# hydrogen_sensors_board.net
KiCad netlist of a schematic drawn in EAGLE
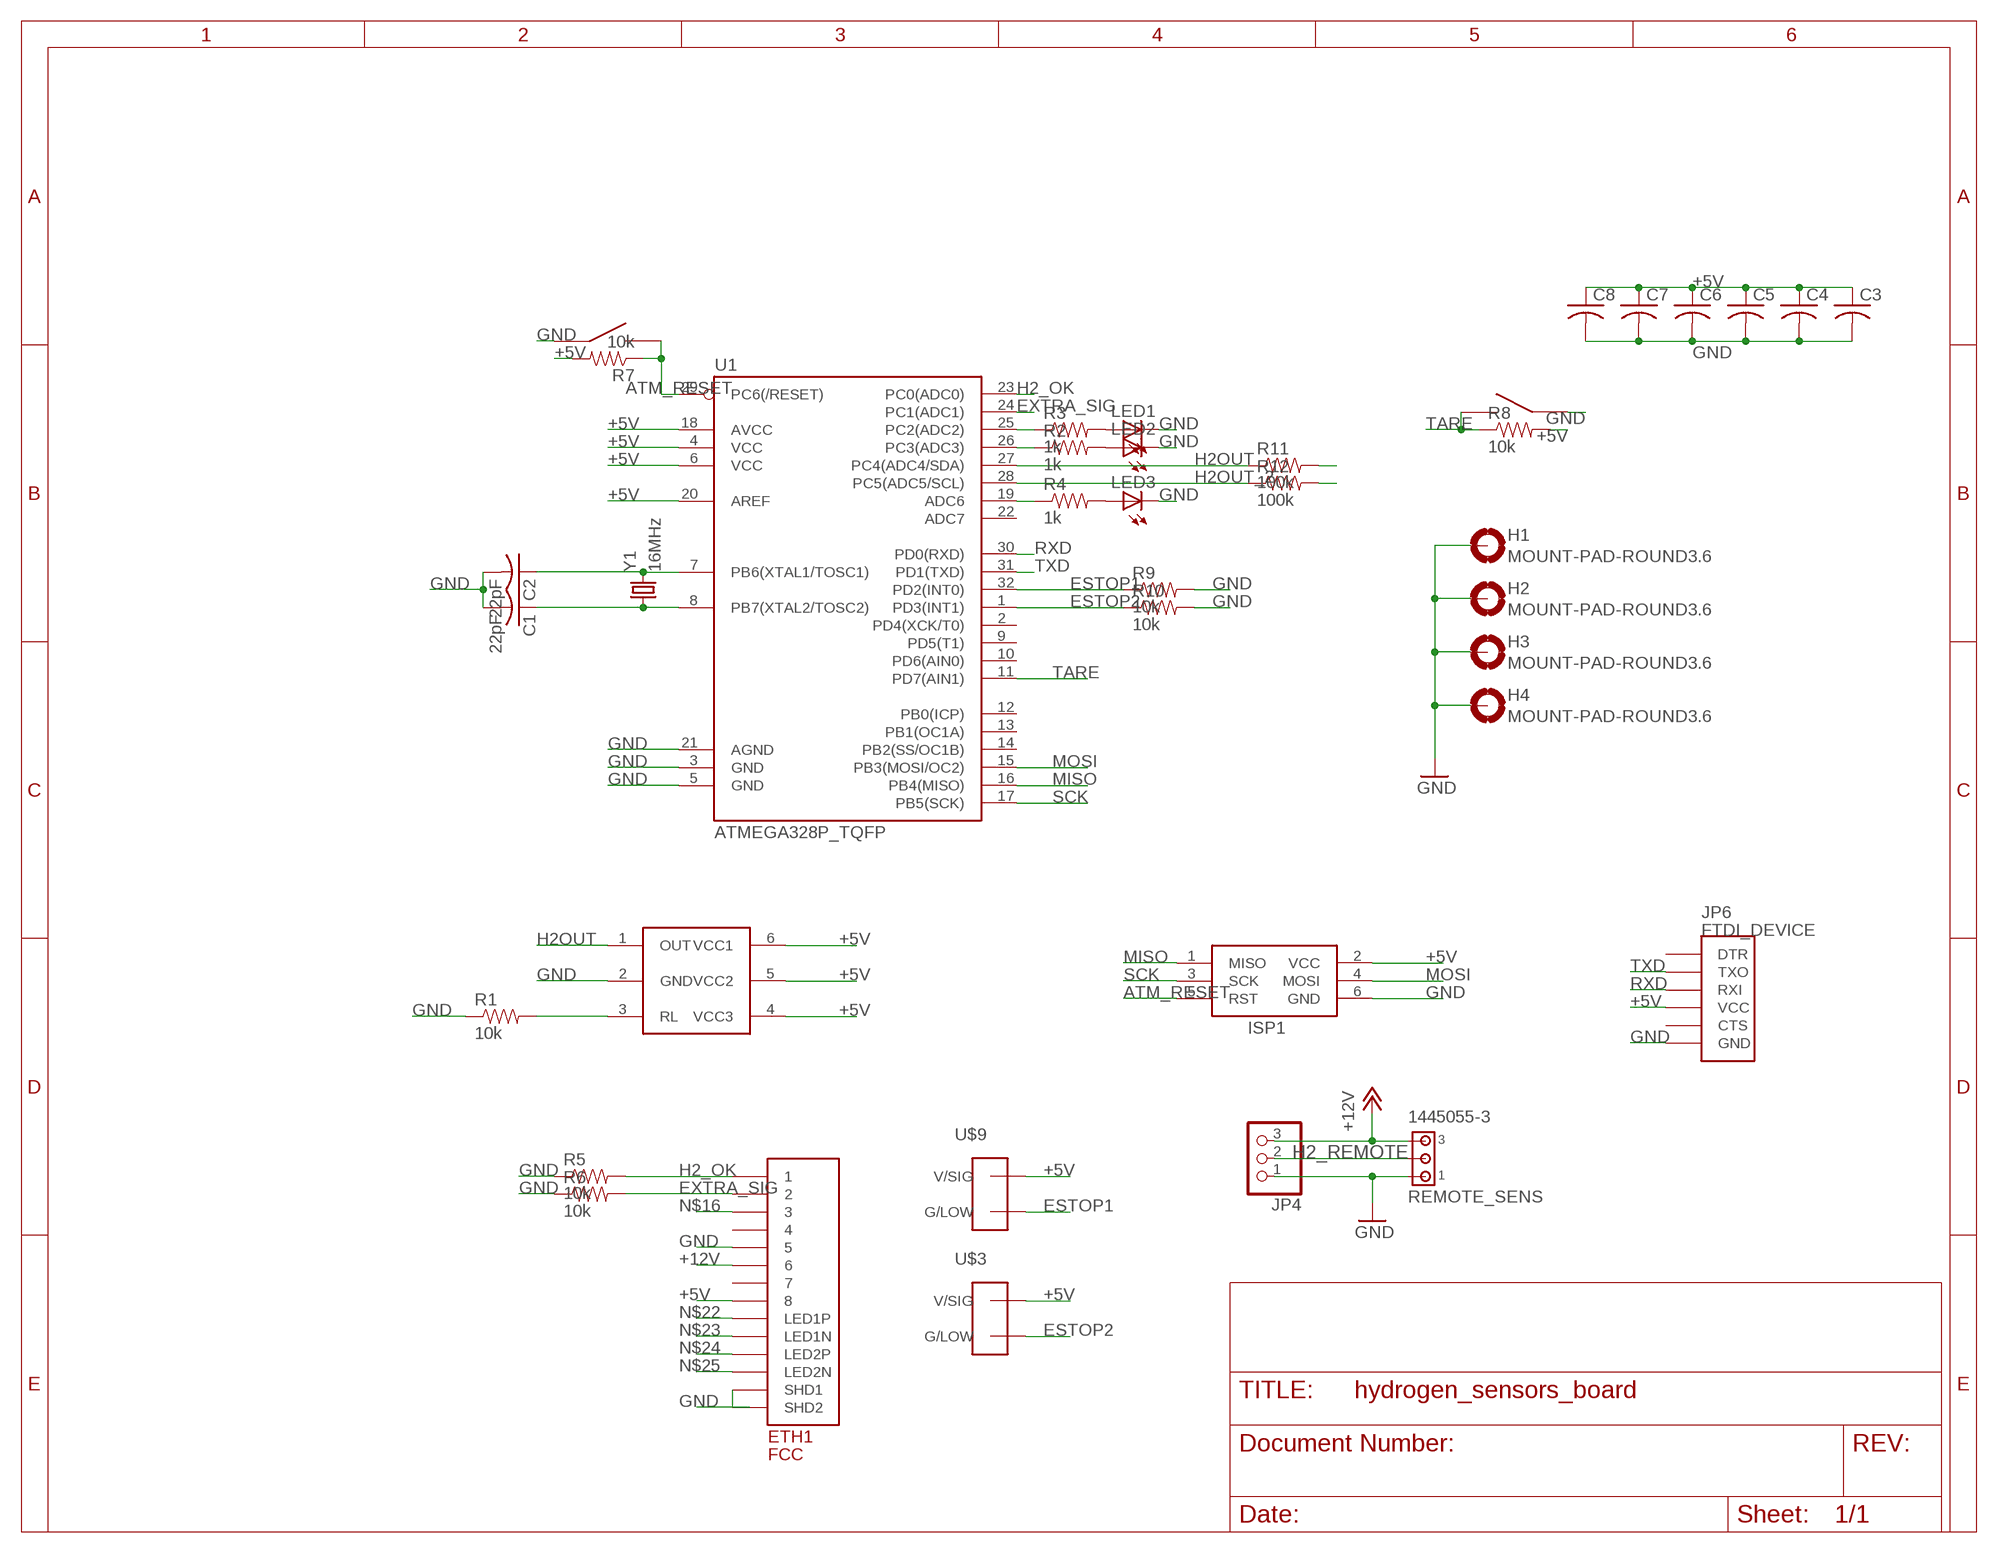
[diagram p0: schematic, sheet 1]

(export (version "E")
  (design (tool "Eeschema 10.0.6"))
  (components
    (comp (ref "C1")
      (value "22pF")
      (footprint "eagle-import:C0603K")
      (libsource (lib "eagle-import") (part "C-USC0603K"))
    )
    (comp (ref "C2")
      (value "22pF")
      (footprint "eagle-import:C0603K")
      (libsource (lib "eagle-import") (part "C-USC0603K"))
    )
    (comp (ref "C3")
      (value "C-USC0603")
      (footprint "eagle-import:C0603")
      (libsource (lib "eagle-import") (part "C-USC0603"))
    )
    (comp (ref "C4")
      (value "C-USC0603")
      (footprint "eagle-import:C0603")
      (libsource (lib "eagle-import") (part "C-USC0603"))
    )
    (comp (ref "C5")
      (value "C-USC0603")
      (footprint "eagle-import:C0603")
      (libsource (lib "eagle-import") (part "C-USC0603"))
    )
    (comp (ref "C6")
      (value "C-USC0603")
      (footprint "eagle-import:C0603")
      (libsource (lib "eagle-import") (part "C-USC0603"))
    )
    (comp (ref "C7")
      (value "C-USC0603")
      (footprint "eagle-import:C0603")
      (libsource (lib "eagle-import") (part "C-USC0603"))
    )
    (comp (ref "C8")
      (value "C-USC0603")
      (footprint "eagle-import:C0603")
      (libsource (lib "eagle-import") (part "C-USC0603"))
    )
    (comp (ref "ETH1")
      (value "FCC")
      (footprint "eagle-import:A122645-ND")
      (libsource (lib "eagle-import") (part "ETHERNET"))
    )
    (comp (ref "H1")
      (value "MOUNT-PAD-ROUND3.6")
      (footprint "eagle-import:3,6-PAD")
      (libsource (lib "eagle-import") (part "MOUNT-PAD-ROUND3.6"))
    )
    (comp (ref "H2")
      (value "MOUNT-PAD-ROUND3.6")
      (footprint "eagle-import:3,6-PAD")
      (libsource (lib "eagle-import") (part "MOUNT-PAD-ROUND3.6"))
    )
    (comp (ref "H3")
      (value "MOUNT-PAD-ROUND3.6")
      (footprint "eagle-import:3,6-PAD")
      (libsource (lib "eagle-import") (part "MOUNT-PAD-ROUND3.6"))
    )
    (comp (ref "H4")
      (value "MOUNT-PAD-ROUND3.6")
      (footprint "eagle-import:3,6-PAD")
      (libsource (lib "eagle-import") (part "MOUNT-PAD-ROUND3.6"))
    )
    (comp (ref "ISP1")
      (value "AVRISP-BOX")
      (footprint "eagle-import:AVRISP-BOX")
      (libsource (lib "eagle-import") (part "AVRISP-BOX"))
    )
    (comp (ref "JP4")
      (value "PINHD-1X3")
      (footprint "eagle-import:1X03")
      (libsource (lib "eagle-import") (part "PINHD-1X3"))
    )
    (comp (ref "JP6")
      (value "FTDI_DEVICE")
      (footprint "eagle-import:FTDI_DEVICE_SIDE")
      (libsource (lib "eagle-import") (part "FTDI_DEVICE"))
    )
    (comp (ref "LED1")
      (value "LEDCHIPLED_0805")
      (footprint "eagle-import:CHIPLED_0805")
      (libsource (lib "eagle-import") (part "LEDCHIPLED_0805"))
    )
    (comp (ref "LED2")
      (value "LEDCHIPLED_0805")
      (footprint "eagle-import:CHIPLED_0805")
      (libsource (lib "eagle-import") (part "LEDCHIPLED_0805"))
    )
    (comp (ref "LED3")
      (value "LEDCHIPLED_0805")
      (footprint "eagle-import:CHIPLED_0805")
      (libsource (lib "eagle-import") (part "LEDCHIPLED_0805"))
    )
    (comp (ref "R1")
      (value "10k")
      (footprint "eagle-import:0603-RES")
      (libsource (lib "eagle-import") (part "RESISTOR0603-RES"))
    )
    (comp (ref "R2")
      (value "1k")
      (footprint "eagle-import:0603-RES")
      (libsource (lib "eagle-import") (part "SparkFun-Resistors_RESISTOR0603-RES"))
    )
    (comp (ref "R3")
      (value "1k")
      (footprint "eagle-import:0603-RES")
      (libsource (lib "eagle-import") (part "SparkFun-Resistors_RESISTOR0603-RES"))
    )
    (comp (ref "R4")
      (value "1k")
      (footprint "eagle-import:0603-RES")
      (libsource (lib "eagle-import") (part "SparkFun-Resistors_RESISTOR0603-RES"))
    )
    (comp (ref "R5")
      (value "10k")
      (footprint "eagle-import:0603-RES")
      (libsource (lib "eagle-import") (part "RESISTOR0603-RES"))
    )
    (comp (ref "R6")
      (value "10k")
      (footprint "eagle-import:0603-RES")
      (libsource (lib "eagle-import") (part "RESISTOR0603-RES"))
    )
    (comp (ref "R7")
      (value "10k")
      (footprint "eagle-import:0603-RES")
      (libsource (lib "eagle-import") (part "SparkFun-Resistors_RESISTOR0603-RES"))
    )
    (comp (ref "R8")
      (value "10k")
      (footprint "eagle-import:0603-RES")
      (libsource (lib "eagle-import") (part "SparkFun-Resistors_RESISTOR0603-RES"))
    )
    (comp (ref "R9")
      (value "10k")
      (footprint "eagle-import:0603-RES")
      (libsource (lib "eagle-import") (part "RESISTOR0603-RES"))
    )
    (comp (ref "R10")
      (value "10k")
      (footprint "eagle-import:0603-RES")
      (libsource (lib "eagle-import") (part "RESISTOR0603-RES"))
    )
    (comp (ref "R11")
      (value "100k")
      (footprint "eagle-import:0603-RES")
      (libsource (lib "eagle-import") (part "SparkFun-Resistors_RESISTOR0603-RES"))
    )
    (comp (ref "R12")
      (value "100k")
      (footprint "eagle-import:0603-RES")
      (libsource (lib "eagle-import") (part "SparkFun-Resistors_RESISTOR0603-RES"))
    )
    (comp (ref "REMOTE_SENS")
      (value "1445055-3")
      (footprint "eagle-import:1445055-3")
      (libsource (lib "eagle-import") (part "1445055-3"))
    )
    (comp (ref "U$1")
      (value "MQ-8MQ-8")
      (footprint "eagle-import:MQ-8")
      (libsource (lib "eagle-import") (part "MQ-8MQ-8"))
    )
    (comp (ref "U$2")
      (value "EG4621CT-ND")
      (footprint "eagle-import:EG4621CT-ND")
      (libsource (lib "eagle-import") (part "EG4621CT-ND"))
    )
    (comp (ref "U$3")
      (value "TE770966")
      (footprint "eagle-import:2X1-MATE-N-LOCK")
      (libsource (lib "eagle-import") (part "TE770966"))
    )
    (comp (ref "U$9")
      (value "TE770966")
      (footprint "eagle-import:2X1-MATE-N-LOCK")
      (libsource (lib "eagle-import") (part "TE770966"))
    )
    (comp (ref "U$10")
      (value "EG4621CT-ND")
      (footprint "eagle-import:EG4621CT-ND")
      (libsource (lib "eagle-import") (part "EG4621CT-ND"))
    )
    (comp (ref "U1")
      (value "ATMEGA328P_TQFP")
      (footprint "eagle-import:TQFP32-08")
      (libsource (lib "eagle-import") (part "ATMEGA328P_TQFP"))
    )
    (comp (ref "Y1")
      (value "16MHz")
      (footprint "eagle-import:HC49US")
      (libsource (lib "eagle-import") (part "CRYSTALHC49US"))
    )
  )
  (nets
    (net (code "1") (name "+12V") (class "Default")
      (node (ref "ETH1") (pin "P$6") (pinfunction "6_P$6") (pintype "bidirectional"))
      (node (ref "JP4") (pin "3") (pinfunction "3_3") (pintype "passive"))
      (node (ref "REMOTE_SENS") (pin "3") (pinfunction "3_3") (pintype "passive"))
    )
    (net (code "2") (name "/+5V") (class "Default")
      (node (ref "C3") (pin "1") (pinfunction "1_1") (pintype "passive"))
      (node (ref "C4") (pin "1") (pinfunction "1_1") (pintype "passive"))
      (node (ref "C5") (pin "1") (pinfunction "1_1") (pintype "passive"))
      (node (ref "C6") (pin "1") (pinfunction "1_1") (pintype "passive"))
      (node (ref "C7") (pin "1") (pinfunction "1_1") (pintype "passive"))
      (node (ref "C8") (pin "1") (pinfunction "1_1") (pintype "passive"))
      (node (ref "ETH1") (pin "P$8") (pinfunction "8_P$8") (pintype "bidirectional"))
      (node (ref "ISP1") (pin "2") (pinfunction "VCC_2") (pintype "power_in"))
      (node (ref "JP6") (pin "P$4") (pinfunction "VCC_P$4") (pintype "bidirectional"))
      (node (ref "R7") (pin "2") (pinfunction "2_2") (pintype "passive"))
      (node (ref "R8") (pin "2") (pinfunction "2_2") (pintype "passive"))
      (node (ref "U$1") (pin "4") (pinfunction "VCC3_4") (pintype "bidirectional"))
      (node (ref "U$1") (pin "5") (pinfunction "VCC2_5") (pintype "bidirectional"))
      (node (ref "U$1") (pin "6") (pinfunction "VCC1_6") (pintype "bidirectional"))
      (node (ref "U$3") (pin "CIRCUIT1") (pinfunction "V/SIG_CIRCUIT1") (pintype "bidirectional"))
      (node (ref "U$9") (pin "CIRCUIT1") (pinfunction "V/SIG_CIRCUIT1") (pintype "bidirectional"))
      (node (ref "U1") (pin "18") (pinfunction "AVCC_18") (pintype "bidirectional"))
      (node (ref "U1") (pin "20") (pinfunction "AREF_20") (pintype "bidirectional"))
      (node (ref "U1") (pin "4") (pinfunction "VCC_4") (pintype "bidirectional"))
      (node (ref "U1") (pin "6") (pinfunction "VCC_6") (pintype "bidirectional"))
    )
    (net (code "3") (name "/ATM_RESET") (class "Default")
      (node (ref "ISP1") (pin "5") (pinfunction "RST_5") (pintype "output"))
      (node (ref "R7") (pin "1") (pinfunction "1_1") (pintype "passive"))
      (node (ref "U$10") (pin "P$3") (pinfunction "P$2_P$3") (pintype "bidirectional"))
      (node (ref "U$10") (pin "P$4") (pinfunction "P$2_P$4") (pintype "bidirectional"))
      (node (ref "U1") (pin "29") (pinfunction "PC6(/RESET)_29") (pintype "bidirectional"))
    )
    (net (code "4") (name "/ESTOP1") (class "Default")
      (node (ref "R9") (pin "1") (pinfunction "1_1") (pintype "passive"))
      (node (ref "U$9") (pin "CIRCUIT2") (pinfunction "G/LOW_CIRCUIT2") (pintype "bidirectional"))
      (node (ref "U1") (pin "32") (pinfunction "PD2(INT0)_32") (pintype "bidirectional"))
    )
    (net (code "5") (name "/ESTOP2") (class "Default")
      (node (ref "R10") (pin "1") (pinfunction "1_1") (pintype "passive"))
      (node (ref "U$3") (pin "CIRCUIT2") (pinfunction "G/LOW_CIRCUIT2") (pintype "bidirectional"))
      (node (ref "U1") (pin "1") (pinfunction "PD3(INT1)_1") (pintype "bidirectional"))
    )
    (net (code "6") (name "/EXTRA_SIG") (class "Default")
      (node (ref "ETH1") (pin "P$2") (pinfunction "2_P$2") (pintype "bidirectional"))
      (node (ref "R6") (pin "2") (pinfunction "2_2") (pintype "passive"))
      (node (ref "U1") (pin "24") (pinfunction "PC1(ADC1)_24") (pintype "bidirectional"))
    )
    (net (code "7") (name "/H2OUT") (class "Default")
      (node (ref "R11") (pin "1") (pinfunction "1_1") (pintype "passive"))
      (node (ref "U$1") (pin "1") (pinfunction "OUT_1") (pintype "bidirectional"))
      (node (ref "U1") (pin "27") (pinfunction "PC4(ADC4/SDA)_27") (pintype "bidirectional"))
    )
    (net (code "8") (name "/H2OUT_2") (class "Default")
      (node (ref "R12") (pin "1") (pinfunction "1_1") (pintype "passive"))
      (node (ref "U1") (pin "28") (pinfunction "PC5(ADC5/SCL)_28") (pintype "bidirectional"))
    )
    (net (code "9") (name "/H2_OK") (class "Default")
      (node (ref "ETH1") (pin "P$1") (pinfunction "1_P$1") (pintype "bidirectional"))
      (node (ref "R5") (pin "2") (pinfunction "2_2") (pintype "passive"))
      (node (ref "U1") (pin "23") (pinfunction "PC0(ADC0)_23") (pintype "bidirectional"))
    )
    (net (code "10") (name "/H2_REMOTE") (class "Default")
      (node (ref "JP4") (pin "2") (pinfunction "2_2") (pintype "passive"))
      (node (ref "REMOTE_SENS") (pin "2") (pinfunction "2_2") (pintype "passive"))
    )
    (net (code "11") (name "/MISO") (class "Default")
      (node (ref "ISP1") (pin "1") (pinfunction "MISO_1") (pintype "input"))
      (node (ref "U1") (pin "16") (pinfunction "PB4(MISO)_16") (pintype "bidirectional"))
    )
    (net (code "12") (name "/MOSI") (class "Default")
      (node (ref "ISP1") (pin "4") (pinfunction "MOSI_4") (pintype "output"))
      (node (ref "U1") (pin "15") (pinfunction "PB3(MOSI/OC2)_15") (pintype "bidirectional"))
    )
    (net (code "13") (name "/N$16") (class "Default")
      (node (ref "ETH1") (pin "P$3") (pinfunction "3_P$3") (pintype "bidirectional"))
    )
    (net (code "14") (name "/N$22") (class "Default")
      (node (ref "ETH1") (pin "P$10") (pinfunction "LED1P_P$10") (pintype "bidirectional"))
    )
    (net (code "15") (name "/N$23") (class "Default")
      (node (ref "ETH1") (pin "P$9") (pinfunction "LED1N_P$9") (pintype "bidirectional"))
    )
    (net (code "16") (name "/N$24") (class "Default")
      (node (ref "ETH1") (pin "P$12") (pinfunction "LED2P_P$12") (pintype "bidirectional"))
    )
    (net (code "17") (name "/N$25") (class "Default")
      (node (ref "ETH1") (pin "P$11") (pinfunction "LED2N_P$11") (pintype "bidirectional"))
    )
    (net (code "18") (name "/RXD") (class "Default")
      (node (ref "JP6") (pin "P$3") (pinfunction "RXI_P$3") (pintype "bidirectional"))
      (node (ref "U1") (pin "30") (pinfunction "PD0(RXD)_30") (pintype "bidirectional"))
    )
    (net (code "19") (name "/SCK") (class "Default")
      (node (ref "ISP1") (pin "3") (pinfunction "SCK_3") (pintype "output"))
      (node (ref "U1") (pin "17") (pinfunction "PB5(SCK)_17") (pintype "bidirectional"))
    )
    (net (code "20") (name "/TARE") (class "Default")
      (node (ref "R8") (pin "1") (pinfunction "1_1") (pintype "passive"))
      (node (ref "U$2") (pin "P$3") (pinfunction "P$2_P$3") (pintype "bidirectional"))
      (node (ref "U$2") (pin "P$4") (pinfunction "P$2_P$4") (pintype "bidirectional"))
      (node (ref "U1") (pin "11") (pinfunction "PD7(AIN1)_11") (pintype "bidirectional"))
    )
    (net (code "21") (name "/TXD") (class "Default")
      (node (ref "JP6") (pin "P$2") (pinfunction "TXO_P$2") (pintype "bidirectional"))
      (node (ref "U1") (pin "31") (pinfunction "PD1(TXD)_31") (pintype "bidirectional"))
    )
    (net (code "22") (name "GND") (class "Default")
      (node (ref "C1") (pin "2") (pinfunction "2_2") (pintype "passive"))
      (node (ref "C2") (pin "2") (pinfunction "2_2") (pintype "passive"))
      (node (ref "C3") (pin "2") (pinfunction "2_2") (pintype "passive"))
      (node (ref "C4") (pin "2") (pinfunction "2_2") (pintype "passive"))
      (node (ref "C5") (pin "2") (pinfunction "2_2") (pintype "passive"))
      (node (ref "C6") (pin "2") (pinfunction "2_2") (pintype "passive"))
      (node (ref "C7") (pin "2") (pinfunction "2_2") (pintype "passive"))
      (node (ref "C8") (pin "2") (pinfunction "2_2") (pintype "passive"))
      (node (ref "ETH1") (pin "P$5") (pinfunction "5_P$5") (pintype "bidirectional"))
      (node (ref "H1") (pin "B3,6") (pinfunction "MOUNT_B3,6") (pintype "passive"))
      (node (ref "H2") (pin "B3,6") (pinfunction "MOUNT_B3,6") (pintype "passive"))
      (node (ref "H3") (pin "B3,6") (pinfunction "MOUNT_B3,6") (pintype "passive"))
      (node (ref "H4") (pin "B3,6") (pinfunction "MOUNT_B3,6") (pintype "passive"))
      (node (ref "ISP1") (pin "6") (pinfunction "GND_6") (pintype "power_in"))
      (node (ref "JP4") (pin "1") (pinfunction "1_1") (pintype "passive"))
      (node (ref "JP6") (pin "P$6") (pinfunction "GND_P$6") (pintype "bidirectional"))
      (node (ref "LED1") (pin "C") (pinfunction "C_C") (pintype "passive"))
      (node (ref "LED2") (pin "C") (pinfunction "C_C") (pintype "passive"))
      (node (ref "LED3") (pin "C") (pinfunction "C_C") (pintype "passive"))
      (node (ref "R1") (pin "1") (pinfunction "1_1") (pintype "passive"))
      (node (ref "R10") (pin "2") (pinfunction "2_2") (pintype "passive"))
      (node (ref "R11") (pin "2") (pinfunction "2_2") (pintype "passive"))
      (node (ref "R12") (pin "2") (pinfunction "2_2") (pintype "passive"))
      (node (ref "R5") (pin "1") (pinfunction "1_1") (pintype "passive"))
      (node (ref "R6") (pin "1") (pinfunction "1_1") (pintype "passive"))
      (node (ref "R9") (pin "2") (pinfunction "2_2") (pintype "passive"))
      (node (ref "REMOTE_SENS") (pin "1") (pinfunction "1_1") (pintype "passive"))
      (node (ref "U$1") (pin "2") (pinfunction "GND_2") (pintype "bidirectional"))
      (node (ref "U$10") (pin "P$1") (pinfunction "P$1_P$1") (pintype "bidirectional"))
      (node (ref "U$10") (pin "P$2") (pinfunction "P$1_P$2") (pintype "bidirectional"))
      (node (ref "U$2") (pin "P$1") (pinfunction "P$1_P$1") (pintype "bidirectional"))
      (node (ref "U$2") (pin "P$2") (pinfunction "P$1_P$2") (pintype "bidirectional"))
      (node (ref "U1") (pin "21") (pinfunction "AGND_21") (pintype "bidirectional"))
      (node (ref "U1") (pin "3") (pinfunction "GND_3") (pintype "bidirectional"))
      (node (ref "U1") (pin "5") (pinfunction "GND_5") (pintype "bidirectional"))
    )
    (net (code "23") (name "Net-(ETH1-SHD1)") (class "Default")
      (node (ref "ETH1") (pin "P$13") (pinfunction "SHD1_P$13") (pintype "bidirectional"))
      (node (ref "ETH1") (pin "P$14") (pinfunction "SHD2_P$14") (pintype "bidirectional"))
    )
    (net (code "24") (name "Net-(LED1-PadA)") (class "Default")
      (node (ref "LED1") (pin "A") (pinfunction "A_A") (pintype "passive"))
      (node (ref "R3") (pin "2") (pinfunction "2_2") (pintype "passive"))
    )
    (net (code "25") (name "Net-(LED2-PadA)") (class "Default")
      (node (ref "LED2") (pin "A") (pinfunction "A_A") (pintype "passive"))
      (node (ref "R2") (pin "2") (pinfunction "2_2") (pintype "passive"))
    )
    (net (code "26") (name "Net-(LED3-PadA)") (class "Default")
      (node (ref "LED3") (pin "A") (pinfunction "A_A") (pintype "passive"))
      (node (ref "R4") (pin "2") (pinfunction "2_2") (pintype "passive"))
    )
    (net (code "27") (name "Net-(U$1-RL)") (class "Default")
      (node (ref "R1") (pin "2") (pinfunction "2_2") (pintype "passive"))
      (node (ref "U$1") (pin "3") (pinfunction "RL_3") (pintype "bidirectional"))
    )
    (net (code "28") (name "Net-(U1-ADC6)") (class "Default")
      (node (ref "R4") (pin "1") (pinfunction "1_1") (pintype "passive"))
      (node (ref "U1") (pin "19") (pinfunction "ADC6_19") (pintype "bidirectional"))
    )
    (net (code "29") (name "Net-(U1-PB6(XTAL1{slash}TOSC1))") (class "Default")
      (node (ref "C2") (pin "1") (pinfunction "1_1") (pintype "passive"))
      (node (ref "U1") (pin "7") (pinfunction "PB6(XTAL1/TOSC1)_7") (pintype "bidirectional"))
      (node (ref "Y1") (pin "2") (pinfunction "2_2") (pintype "passive"))
    )
    (net (code "30") (name "Net-(U1-PB7(XTAL2{slash}TOSC2))") (class "Default")
      (node (ref "C1") (pin "1") (pinfunction "1_1") (pintype "passive"))
      (node (ref "U1") (pin "8") (pinfunction "PB7(XTAL2/TOSC2)_8") (pintype "bidirectional"))
      (node (ref "Y1") (pin "1") (pinfunction "1_1") (pintype "passive"))
    )
    (net (code "31") (name "Net-(U1-PC2(ADC2))") (class "Default")
      (node (ref "R3") (pin "1") (pinfunction "1_1") (pintype "passive"))
      (node (ref "U1") (pin "25") (pinfunction "PC2(ADC2)_25") (pintype "bidirectional"))
    )
    (net (code "32") (name "Net-(U1-PC3(ADC3))") (class "Default")
      (node (ref "R2") (pin "1") (pinfunction "1_1") (pintype "passive"))
      (node (ref "U1") (pin "26") (pinfunction "PC3(ADC3)_26") (pintype "bidirectional"))
    )
    (net (code "33") (name "unconnected-(ETH1-4-PadP$4)") (class "Default")
      (node (ref "ETH1") (pin "P$4") (pinfunction "4_P$4") (pintype "bidirectional"))
    )
    (net (code "34") (name "unconnected-(ETH1-7-PadP$7)") (class "Default")
      (node (ref "ETH1") (pin "P$7") (pinfunction "7_P$7") (pintype "bidirectional"))
    )
    (net (code "35") (name "unconnected-(JP6-CTS-PadP$5)") (class "Default")
      (node (ref "JP6") (pin "P$5") (pinfunction "CTS_P$5") (pintype "bidirectional"))
    )
    (net (code "36") (name "unconnected-(JP6-DTR-PadP$1)") (class "Default")
      (node (ref "JP6") (pin "P$1") (pinfunction "DTR_P$1") (pintype "bidirectional"))
    )
    (net (code "37") (name "unconnected-(U1-ADC7-Pad22)") (class "Default")
      (node (ref "U1") (pin "22") (pinfunction "ADC7_22") (pintype "bidirectional"))
    )
    (net (code "38") (name "unconnected-(U1-PB0(ICP)-Pad12)") (class "Default")
      (node (ref "U1") (pin "12") (pinfunction "PB0(ICP)_12") (pintype "bidirectional"))
    )
    (net (code "39") (name "unconnected-(U1-PB1(OC1A)-Pad13)") (class "Default")
      (node (ref "U1") (pin "13") (pinfunction "PB1(OC1A)_13") (pintype "bidirectional"))
    )
    (net (code "40") (name "unconnected-(U1-PB2(SS{slash}OC1B)-Pad14)") (class "Default")
      (node (ref "U1") (pin "14") (pinfunction "PB2(SS/OC1B)_14") (pintype "bidirectional"))
    )
    (net (code "41") (name "unconnected-(U1-PD4(XCK{slash}T0)-Pad2)") (class "Default")
      (node (ref "U1") (pin "2") (pinfunction "PD4(XCK/T0)_2") (pintype "bidirectional"))
    )
    (net (code "42") (name "unconnected-(U1-PD5(T1)-Pad9)") (class "Default")
      (node (ref "U1") (pin "9") (pinfunction "PD5(T1)_9") (pintype "bidirectional"))
    )
    (net (code "43") (name "unconnected-(U1-PD6(AIN0)-Pad10)") (class "Default")
      (node (ref "U1") (pin "10") (pinfunction "PD6(AIN0)_10") (pintype "bidirectional"))
    )
  )
)
